# IPM_12V.net
KiCad netlist of a schematic drawn in EasyEDA Pro
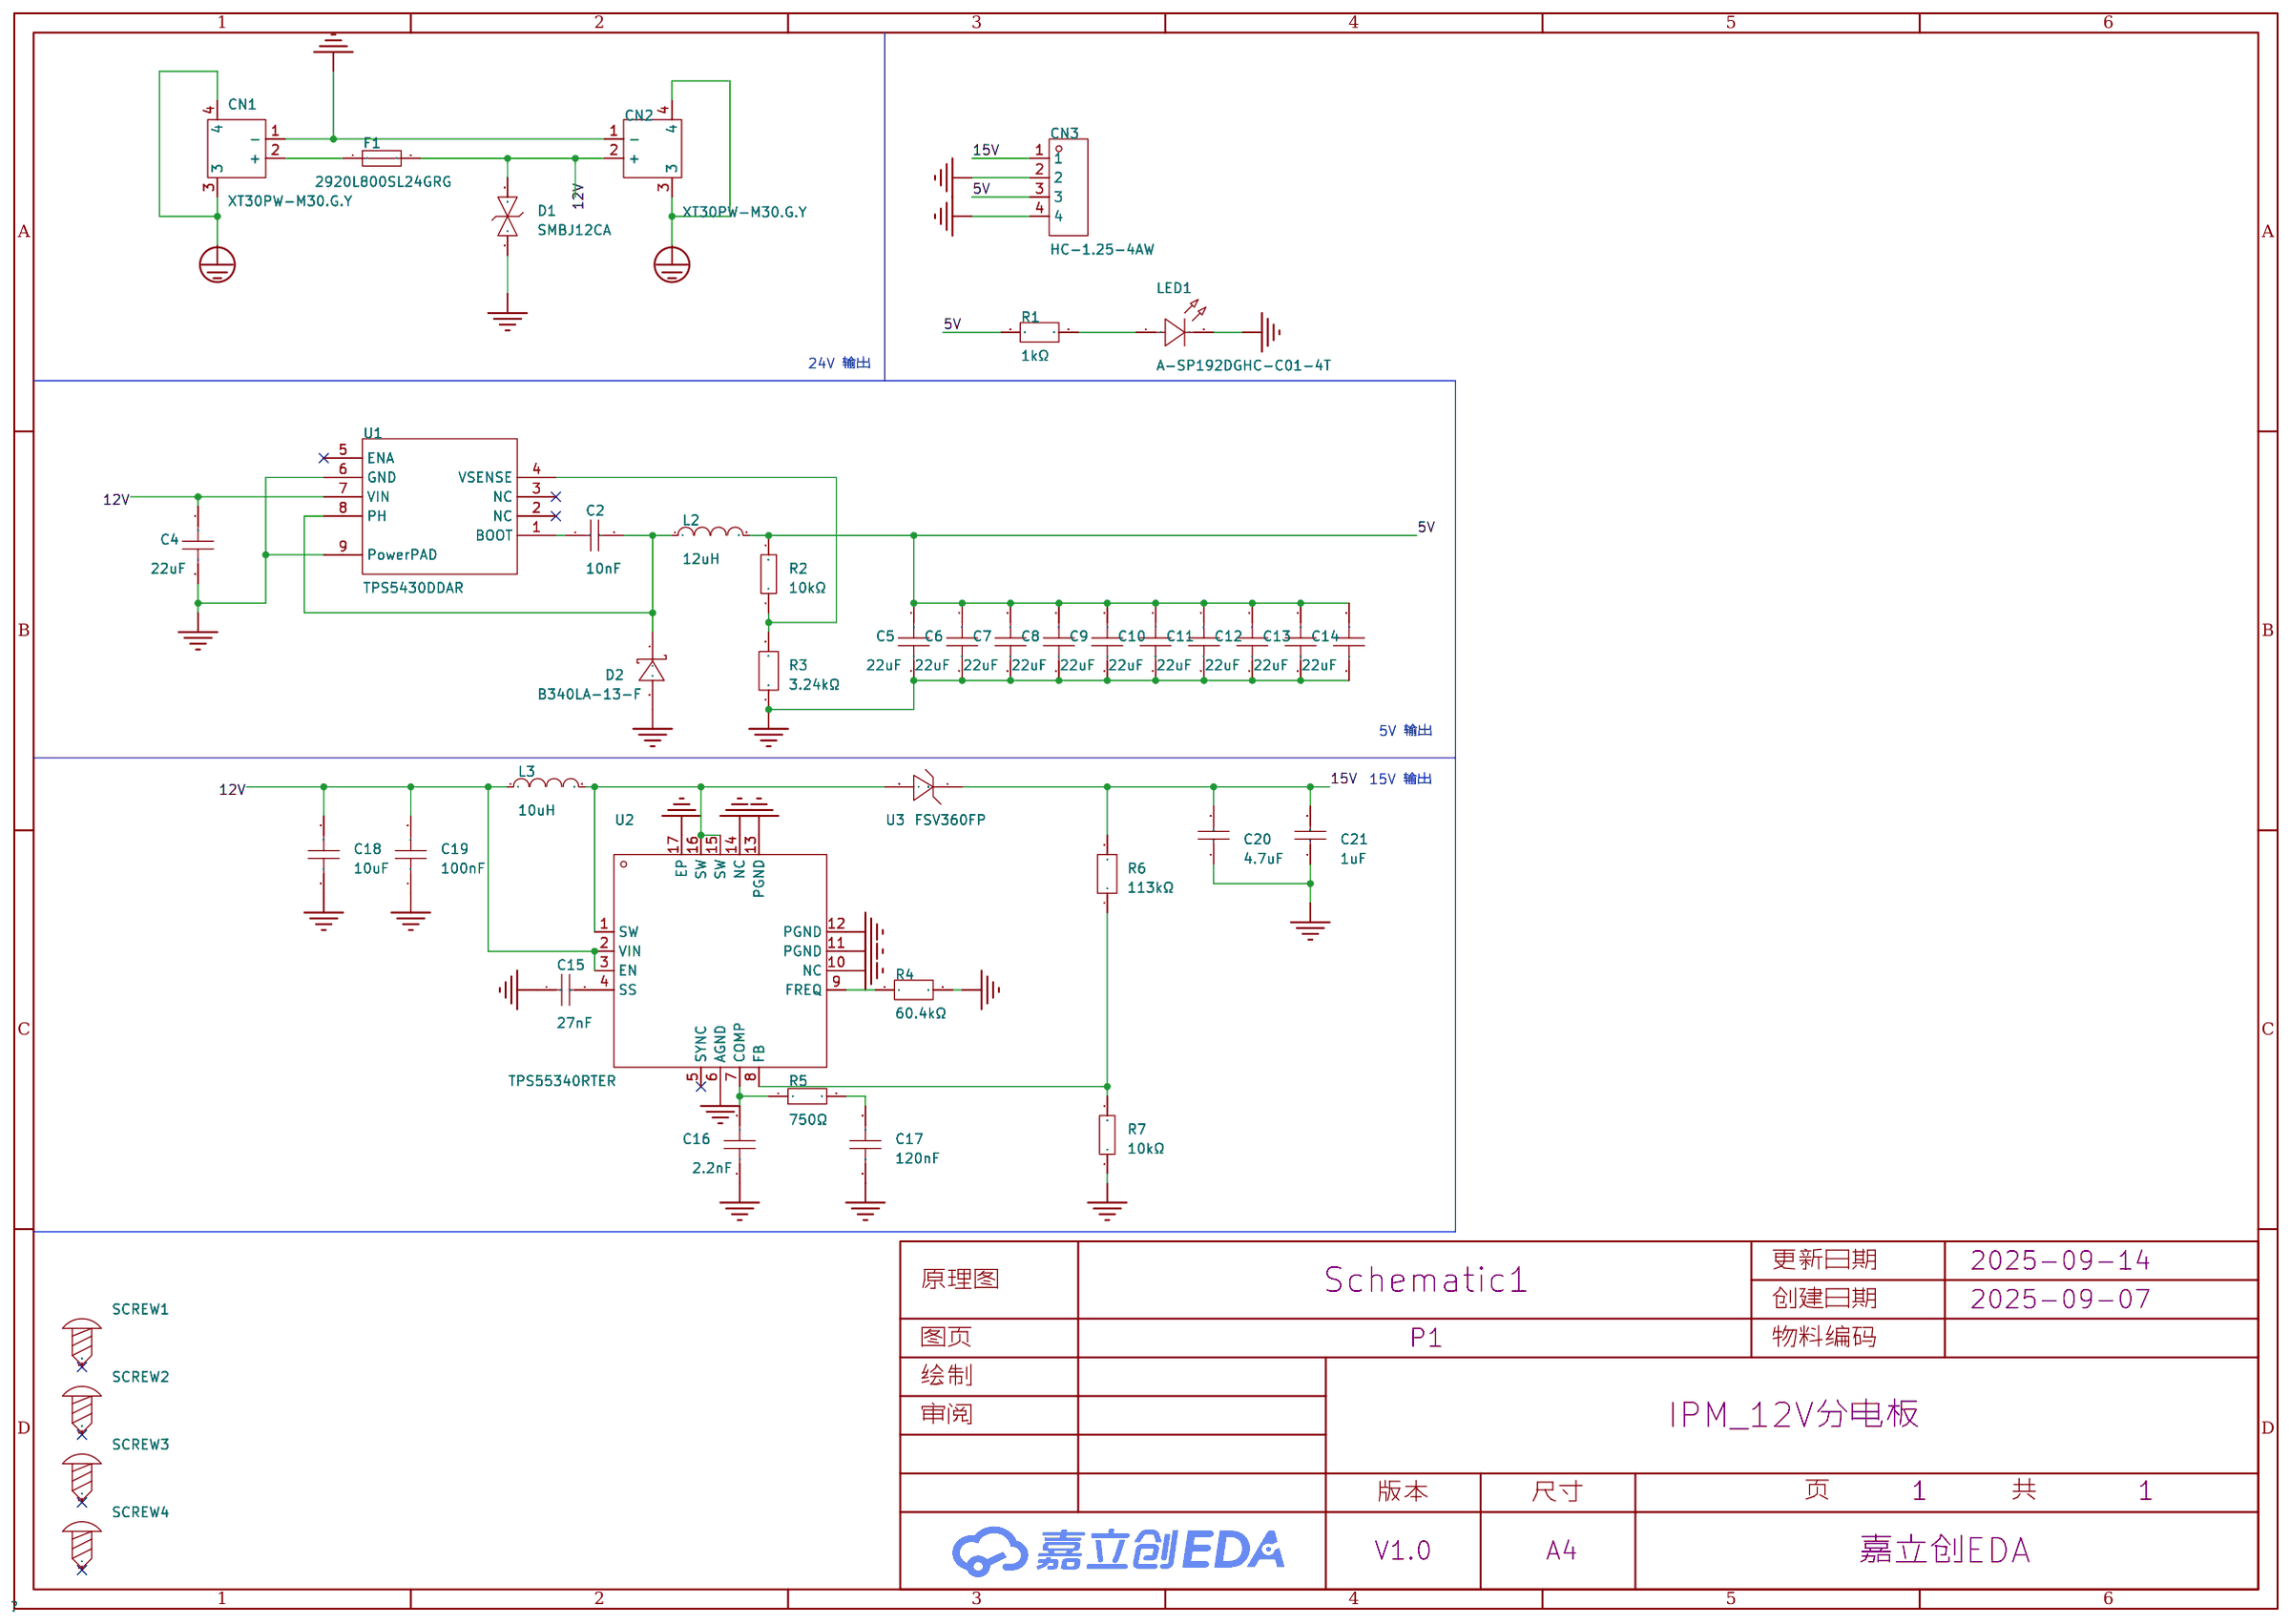
[diagram p0: schematic sheet]

(export (version "E")
  (design (tool "Eeschema 10.0.6"))
  (components
    (comp (ref "C2")
      (value "10nF")
      (footprint "easyedapro:C0603")
      (description "容值:10nF;精度:±10%;额定电压:50V;温度系数:X7R;")
      (fields
        (field (name "Manufacturer Part") "CL10B103KB8NNNC")
        (field (name "Manufacturer") "SAMSUNG(三星)")
      )
      (libsource (lib "easyedapro") (part "CL10B103KB8NNNC"))
    )
    (comp (ref "C4")
      (value "22uF")
      (footprint "easyedapro:C0603")
      (description "容值:22uF;精度:±20%;额定电压:16V;温度系数:X5R;")
      (fields
        (field (name "Manufacturer Part") "CL10A226MO7JZNC")
        (field (name "Manufacturer") "SAMSUNG(三星)")
      )
      (libsource (lib "easyedapro") (part "CL10A226MO7JZNC"))
    )
    (comp (ref "C5")
      (value "22uF")
      (footprint "easyedapro:C0603")
      (description "容值:22uF;精度:±20%;额定电压:16V;温度系数:X5R;")
      (fields
        (field (name "Manufacturer Part") "CL10A226MO7JZNC")
        (field (name "Manufacturer") "SAMSUNG(三星)")
      )
      (libsource (lib "easyedapro") (part "CL10A226MO7JZNC"))
    )
    (comp (ref "C6")
      (value "22uF")
      (footprint "easyedapro:C0603")
      (description "容值:22uF;精度:±20%;额定电压:16V;温度系数:X5R;")
      (fields
        (field (name "Manufacturer Part") "CL10A226MO7JZNC")
        (field (name "Manufacturer") "SAMSUNG(三星)")
      )
      (libsource (lib "easyedapro") (part "CL10A226MO7JZNC"))
    )
    (comp (ref "C7")
      (value "22uF")
      (footprint "easyedapro:C0603")
      (description "容值:22uF;精度:±20%;额定电压:16V;温度系数:X5R;")
      (fields
        (field (name "Manufacturer Part") "CL10A226MO7JZNC")
        (field (name "Manufacturer") "SAMSUNG(三星)")
      )
      (libsource (lib "easyedapro") (part "CL10A226MO7JZNC"))
    )
    (comp (ref "C8")
      (value "22uF")
      (footprint "easyedapro:C0603")
      (description "容值:22uF;精度:±20%;额定电压:16V;温度系数:X5R;")
      (fields
        (field (name "Manufacturer Part") "CL10A226MO7JZNC")
        (field (name "Manufacturer") "SAMSUNG(三星)")
      )
      (libsource (lib "easyedapro") (part "CL10A226MO7JZNC"))
    )
    (comp (ref "C9")
      (value "22uF")
      (footprint "easyedapro:C0603")
      (description "容值:22uF;精度:±20%;额定电压:16V;温度系数:X5R;")
      (fields
        (field (name "Manufacturer Part") "CL10A226MO7JZNC")
        (field (name "Manufacturer") "SAMSUNG(三星)")
      )
      (libsource (lib "easyedapro") (part "CL10A226MO7JZNC"))
    )
    (comp (ref "C10")
      (value "22uF")
      (footprint "easyedapro:C0603")
      (description "容值:22uF;精度:±20%;额定电压:16V;温度系数:X5R;")
      (fields
        (field (name "Manufacturer Part") "CL10A226MO7JZNC")
        (field (name "Manufacturer") "SAMSUNG(三星)")
      )
      (libsource (lib "easyedapro") (part "CL10A226MO7JZNC"))
    )
    (comp (ref "C11")
      (value "22uF")
      (footprint "easyedapro:C0603")
      (description "容值:22uF;精度:±20%;额定电压:16V;温度系数:X5R;")
      (fields
        (field (name "Manufacturer Part") "CL10A226MO7JZNC")
        (field (name "Manufacturer") "SAMSUNG(三星)")
      )
      (libsource (lib "easyedapro") (part "CL10A226MO7JZNC"))
    )
    (comp (ref "C12")
      (value "22uF")
      (footprint "easyedapro:C0603")
      (description "容值:22uF;精度:±20%;额定电压:16V;温度系数:X5R;")
      (fields
        (field (name "Manufacturer Part") "CL10A226MO7JZNC")
        (field (name "Manufacturer") "SAMSUNG(三星)")
      )
      (libsource (lib "easyedapro") (part "CL10A226MO7JZNC"))
    )
    (comp (ref "C13")
      (value "22uF")
      (footprint "easyedapro:C0603")
      (description "容值:22uF;精度:±20%;额定电压:16V;温度系数:X5R;")
      (fields
        (field (name "Manufacturer Part") "CL10A226MO7JZNC")
        (field (name "Manufacturer") "SAMSUNG(三星)")
      )
      (libsource (lib "easyedapro") (part "CL10A226MO7JZNC"))
    )
    (comp (ref "C14")
      (value "22uF")
      (footprint "easyedapro:C0603")
      (description "容值:22uF;精度:±20%;额定电压:16V;温度系数:X5R;")
      (fields
        (field (name "Manufacturer Part") "CL10A226MO7JZNC")
        (field (name "Manufacturer") "SAMSUNG(三星)")
      )
      (libsource (lib "easyedapro") (part "CL10A226MO7JZNC"))
    )
    (comp (ref "C15")
      (value "27nF")
      (footprint "easyedapro:C0603")
      (description "容值:27nF;精度:±10%;额定电压:50V;温度系数:X7R;")
      (fields
        (field (name "Manufacturer Part") "CC0603KRX7R9BB273")
        (field (name "Manufacturer") "YAGEO(国巨)")
      )
      (libsource (lib "easyedapro") (part "CC0603KRX7R9BB273"))
    )
    (comp (ref "C16")
      (value "2.2nF")
      (footprint "easyedapro:C0603")
      (description "容值:2.2nF;精度:±5%;额定电压:50V;材质(温度系数):C0G;")
      (fields
        (field (name "Manufacturer Part") "GRM1885C1H222JA01D")
        (field (name "Manufacturer") "muRata(村田)")
      )
      (libsource (lib "easyedapro") (part "GRM1885C1H222JA01D"))
    )
    (comp (ref "C17")
      (value "120nF")
      (footprint "easyedapro:C0603")
      (description "容值:120nF;精度:±10%;额定电压:50V;温度系数:X7R;")
      (fields
        (field (name "Manufacturer Part") "CGA0603X7R124K500JT")
        (field (name "Manufacturer") "HRE(芯声)")
      )
      (libsource (lib "easyedapro") (part "CGA0603X7R124K500JT"))
    )
    (comp (ref "C18")
      (value "10uF")
      (footprint "easyedapro:C0603")
      (description "容值:10uF;精度:±20%;额定电压:25V;温度系数:X5R;")
      (fields
        (field (name "Manufacturer Part") "CL10A106MA8NRNC")
        (field (name "Manufacturer") "SAMSUNG(三星)")
      )
      (libsource (lib "easyedapro") (part "CL10A106MA8NRNC"))
    )
    (comp (ref "C19")
      (value "100nF")
      (footprint "easyedapro:C0603")
      (description "容值:100nF;精度:±10%;额定电压:50V;温度系数:X7R;")
      (fields
        (field (name "Manufacturer Part") "CL10B104KB8NNNC")
        (field (name "Manufacturer") "SAMSUNG(三星)")
      )
      (libsource (lib "easyedapro") (part "CL10B104KB8NNNC"))
    )
    (comp (ref "C20")
      (value "4.7uF")
      (footprint "easyedapro:C0805")
      (description "容值:4.7uF;精度:±10%;额定电压:50V;温度系数:X5R;")
      (fields
        (field (name "Manufacturer Part") "CL21A475KBQNNNE")
        (field (name "Manufacturer") "SAMSUNG(三星)")
      )
      (libsource (lib "easyedapro") (part "CL21A475KBQNNNE"))
    )
    (comp (ref "C21")
      (value "1uF")
      (footprint "easyedapro:C0805")
      (description "容值:1uF;精度:±10%;额定电压:50V;温度系数:X7R;")
      (fields
        (field (name "Manufacturer Part") "CL21B105KBFNNNE")
        (field (name "Manufacturer") "SAMSUNG(三星)")
      )
      (libsource (lib "easyedapro") (part "CL21B105KBFNNNE"))
    )
    (comp (ref "CN1")
      (value "XT30PW-M30.G.Y")
      (footprint "easyedapro:CONN-TH_XT30PW-M")
      (description "类别:-;类型1:-;")
      (fields (field (name "Manufacturer") "AMASS(艾迈斯)"))
      (libsource (lib "easyedapro") (part "XT30PW-M"))
    )
    (comp (ref "CN2")
      (value "XT30PW-M30.G.Y")
      (footprint "easyedapro:CONN-TH_XT30PW-M")
      (description "类别:-;类型1:-;")
      (fields (field (name "Manufacturer") "AMASS(艾迈斯)"))
      (libsource (lib "easyedapro") (part "XT30PW-M"))
    )
    (comp (ref "CN3")
      (value "HC-1.25-4AW")
      (footprint "easyedapro:CONN-TH_4P-P1.25_HCTL_HC-1.25-4AW")
      (fields (field (name "Manufacturer") "HCTL(华灿天禄)"))
      (libsource (lib "easyedapro") (part "HC-1.25-4AW"))
    )
    (comp (ref "D1")
      (value "SMBJ12CA")
      (footprint "easyedapro:SMB_L4.6-W3.6-LS5.4-BI")
      (fields (field (name "Manufacturer") "R+O(宏嘉诚)"))
      (libsource (lib "easyedapro") (part "SMBJ12CA_C19077566"))
    )
    (comp (ref "D2")
      (value "B340LA-13-F")
      (footprint "easyedapro:SMA_L4.3-W2.6-LS5.2-RD")
      (description "正向压降(Vf):450mV@3A;直流反向耐压(Vr):40V;平均整流电流(Io):3A;")
      (fields (field (name "Manufacturer") "DIODES(美台)"))
      (libsource (lib "easyedapro") (part "B340LA-13-F"))
    )
    (comp (ref "F1")
      (value "2920L800SL24GRG")
      (footprint "easyedapro:F2920")
      (description "耐压(Vmax):24V;最大电流(Imax):50A;保持电流(Ihold):8A;跳闸电流(Itrip):16A;")
      (fields (field (name "Manufacturer") "LUTE(陆特)"))
      (libsource (lib "easyedapro") (part "2920L800SL24GRG"))
    )
    (comp (ref "L2")
      (value "12uH")
      (footprint "easyedapro:IND-SMD_L8.0-W8.0_FNR80XXS")
      (description "电感值:12uH;精度:±20%;额定电流:3A;饱和电流(Isat):4A;类型:磁胶屏蔽绕线合金电感;")
      (fields (field (name "Manufacturer Part") "FNR8040S120MT") (field (name "Manufacturer") "cjiang(长江微电)"))
      (libsource (lib "easyedapro") (part "FNR8040S120MT"))
    )
    (comp (ref "L3")
      (value "10uH")
      (footprint "easyedapro:IND-SMD_L5.4-W5.2_FXL0530")
      (description "电感值:10uH;精度:±20%;额定电流:3.2A;饱和电流(Isat):3.5A;类型:一体成型电感;")
      (fields (field (name "Manufacturer Part") "FXL0530-100-M") (field (name "Manufacturer") "cjiang(长江微电)"))
      (libsource (lib "easyedapro") (part "FXL0530-100-M"))
    )
    (comp (ref "LED1")
      (value "A-SP192DGHC-C01-4T")
      (footprint "easyedapro:LED0603-FD")
      (fields (field (name "Manufacturer") "Amicc(欧密格光电)"))
      (libsource (lib "easyedapro") (part "A-SP192DGHC-C01-4T"))
    )
    (comp (ref "R1")
      (value "1kΩ")
      (footprint "easyedapro:R0603")
      (description "电阻类型:厚膜电阻;阻值:1kΩ;精度:±1%;功率:100mW;工作电压:75V;温度系数:±100ppm/°C;")
      (fields (field (name "Manufacturer Part") "FRC0603F1001TS") (field (name "Manufacturer") "FOJAN(富捷)"))
      (libsource (lib "easyedapro") (part "FRC0603F1001TS"))
    )
    (comp (ref "R2")
      (value "10kΩ")
      (footprint "easyedapro:R0603")
      (description "电阻类型:厚膜电阻;阻值:10kΩ;精度:±1%;功率:100mW;工作电压:75V;温度系数:±100ppm/°C;")
      (fields
        (field (name "Manufacturer Part") "0603WAF1002T5E")
        (field (name "Manufacturer") "UNI-ROYAL(厚声)")
      )
      (libsource (lib "easyedapro") (part "0603WAF1002T5E"))
    )
    (comp (ref "R3")
      (value "3.24kΩ")
      (footprint "easyedapro:R0603")
      (description "电阻类型:厚膜电阻;阻值:3.24kΩ;精度:±1%;功率:100mW;工作电压:75V;温度系数:±100ppm/°C;")
      (fields (field (name "Manufacturer Part") "FRC0603F3241TS") (field (name "Manufacturer") "FOJAN(富捷)"))
      (libsource (lib "easyedapro") (part "FRC0603F3241TS"))
    )
    (comp (ref "R4")
      (value "60.4kΩ")
      (footprint "easyedapro:R0603")
      (description "电阻类型:薄膜电阻;阻值:60.4kΩ;精度:±0.1%;功率:100mW;温度系数:±25ppm/°C;")
      (fields (field (name "Manufacturer Part") "RT0603BRD0760K4L") (field (name "Manufacturer") "YAGEO(国巨)"))
      (libsource (lib "easyedapro") (part "RT0603BRD0760K4L"))
    )
    (comp (ref "R5")
      (value "750Ω")
      (footprint "easyedapro:R0603")
      (description "电阻类型:薄膜电阻;阻值:750Ω;精度:±0.1%;功率:100mW;工作电压:100V;温度系数:±25ppm/°C;")
      (fields (field (name "Manufacturer Part") "PTFR0603B750RP9") (field (name "Manufacturer") "RESI(开步睿思)"))
      (libsource (lib "easyedapro") (part "PTFR0603B750RP9"))
    )
    (comp (ref "R6")
      (value "113kΩ")
      (footprint "easyedapro:R0603")
      (description "电阻类型:薄膜电阻;阻值:113kΩ;精度:±0.1%;功率:100mW;工作电压:75V;温度系数:±25ppm/°C;")
      (fields (field (name "Manufacturer Part") "RT0603BRD07113KL") (field (name "Manufacturer") "YAGEO(国巨)"))
      (libsource (lib "easyedapro") (part "RT0603BRD07113KL"))
    )
    (comp (ref "R7")
      (value "10kΩ")
      (footprint "easyedapro:R0603")
      (description "电阻类型:厚膜电阻;阻值:10kΩ;精度:±1%;功率:100mW;工作电压:75V;温度系数:±100ppm/°C;")
      (fields
        (field (name "Manufacturer Part") "0603WAF1002T5E")
        (field (name "Manufacturer") "UNI-ROYAL(厚声)")
      )
      (libsource (lib "easyedapro") (part "0603WAF1002T5E"))
    )
    (comp (ref "SCREW1")
      (value "~")
      (footprint "easyedapro:M2螺丝")
      (libsource (lib "easyedapro") (part "螺丝孔"))
    )
    (comp (ref "SCREW2")
      (value "~")
      (footprint "easyedapro:M2螺丝")
      (libsource (lib "easyedapro") (part "螺丝孔"))
    )
    (comp (ref "SCREW3")
      (value "~")
      (footprint "easyedapro:M2螺丝")
      (libsource (lib "easyedapro") (part "螺丝孔"))
    )
    (comp (ref "SCREW4")
      (value "~")
      (footprint "easyedapro:M2螺丝")
      (libsource (lib "easyedapro") (part "螺丝孔"))
    )
    (comp (ref "U1")
      (value "TPS5430DDAR")
      (footprint "easyedapro:ESOP-8_L4.9-W3.9-P1.27-LS6.0-TL-EP")
      (description "功能类型:降压型;输出类型:可调;工作电压:5.5V~36V;输出电压:1.221V~32.04V;输出电流:3A;")
      (fields (field (name "Manufacturer") "TI(德州仪器)"))
      (libsource (lib "easyedapro") (part "TPS5430DDAR"))
    )
    (comp (ref "U2")
      (value "TPS55340RTER")
      (footprint "easyedapro:VQFN-16_L3.0-W3.0-P0.50-BL-EP1.7")
      (description "功能类型:升压型;输出类型:可调;工作电压:2.9V~32V;输出电压:2.9V~38V;输出电流:5.25A;")
      (fields (field (name "Manufacturer") "TI(德州仪器)"))
      (libsource (lib "easyedapro") (part "TPS55340RTER"))
    )
    (comp (ref "U3")
      (value "FSV360FP")
      (footprint "easyedapro:POWERDI-123_L2.8-W1.8-LS3.7-RD-1")
      (description "二极管配置:独立式;正向压降(Vf):650mV@3A;直流反向耐压(Vr):60V;整流电流:3A;")
      (fields (field (name "Manufacturer") "onsemi(安森美)"))
      (libsource (lib "easyedapro") (part "FSV360FP"))
    )
  )
  (nets
    (net (code "1") (name "/5V") (class "Default")
      (node (ref "C10") (pin "1") (pinfunction "1_1") (pintype "unspecified"))
      (node (ref "C11") (pin "1") (pinfunction "1_1") (pintype "unspecified"))
      (node (ref "C12") (pin "1") (pinfunction "1_1") (pintype "unspecified"))
      (node (ref "C13") (pin "1") (pinfunction "1_1") (pintype "unspecified"))
      (node (ref "C14") (pin "1") (pinfunction "1_1") (pintype "unspecified"))
      (node (ref "C5") (pin "1") (pinfunction "1_1") (pintype "unspecified"))
      (node (ref "C6") (pin "1") (pinfunction "1_1") (pintype "unspecified"))
      (node (ref "C7") (pin "1") (pinfunction "1_1") (pintype "unspecified"))
      (node (ref "C8") (pin "1") (pinfunction "1_1") (pintype "unspecified"))
      (node (ref "C9") (pin "1") (pinfunction "1_1") (pintype "unspecified"))
      (node (ref "CN3") (pin "3") (pinfunction "3_3") (pintype "unspecified"))
      (node (ref "L2") (pin "2") (pinfunction "2_2") (pintype "unspecified"))
      (node (ref "R1") (pin "1") (pinfunction "1_1") (pintype "unspecified"))
      (node (ref "R2") (pin "2") (pinfunction "2_2") (pintype "input"))
    )
    (net (code "2") (name "/12V") (class "Default")
      (node (ref "C18") (pin "2") (pinfunction "2_2") (pintype "unspecified"))
      (node (ref "C19") (pin "2") (pinfunction "2_2") (pintype "unspecified"))
      (node (ref "C4") (pin "1") (pinfunction "1_1") (pintype "unspecified"))
      (node (ref "CN2") (pin "2") (pinfunction "+_2") (pintype "unspecified"))
      (node (ref "D1") (pin "2") (pinfunction "2_2") (pintype "unspecified"))
      (node (ref "F1") (pin "2") (pinfunction "2_2") (pintype "unspecified"))
      (node (ref "L3") (pin "1") (pinfunction "1_1") (pintype "unspecified"))
      (node (ref "U1") (pin "7") (pinfunction "VIN_7") (pintype "unspecified"))
      (node (ref "U2") (pin "2") (pinfunction "VIN_2") (pintype "unspecified"))
      (node (ref "U2") (pin "3") (pinfunction "EN_3") (pintype "unspecified"))
    )
    (net (code "3") (name "/15V") (class "Default")
      (node (ref "C20") (pin "2") (pinfunction "2_2") (pintype "input"))
      (node (ref "C21") (pin "2") (pinfunction "2_2") (pintype "input"))
      (node (ref "CN3") (pin "1") (pinfunction "1_1") (pintype "unspecified"))
      (node (ref "R6") (pin "2") (pinfunction "2_2") (pintype "unspecified"))
      (node (ref "U3") (pin "1") (pinfunction "C_1") (pintype "unspecified"))
    )
    (net (code "4") (name "GND") (class "Default")
      (node (ref "C10") (pin "2") (pinfunction "2_2") (pintype "unspecified"))
      (node (ref "C11") (pin "2") (pinfunction "2_2") (pintype "unspecified"))
      (node (ref "C12") (pin "2") (pinfunction "2_2") (pintype "unspecified"))
      (node (ref "C13") (pin "2") (pinfunction "2_2") (pintype "unspecified"))
      (node (ref "C14") (pin "2") (pinfunction "2_2") (pintype "unspecified"))
      (node (ref "C15") (pin "1") (pinfunction "1_1") (pintype "input"))
      (node (ref "C16") (pin "1") (pinfunction "1_1") (pintype "unspecified"))
      (node (ref "C17") (pin "1") (pinfunction "1_1") (pintype "unspecified"))
      (node (ref "C18") (pin "1") (pinfunction "1_1") (pintype "unspecified"))
      (node (ref "C19") (pin "1") (pinfunction "1_1") (pintype "unspecified"))
      (node (ref "C20") (pin "1") (pinfunction "1_1") (pintype "input"))
      (node (ref "C21") (pin "1") (pinfunction "1_1") (pintype "input"))
      (node (ref "C4") (pin "2") (pinfunction "2_2") (pintype "unspecified"))
      (node (ref "C5") (pin "2") (pinfunction "2_2") (pintype "unspecified"))
      (node (ref "C6") (pin "2") (pinfunction "2_2") (pintype "unspecified"))
      (node (ref "C7") (pin "2") (pinfunction "2_2") (pintype "unspecified"))
      (node (ref "C8") (pin "2") (pinfunction "2_2") (pintype "unspecified"))
      (node (ref "C9") (pin "2") (pinfunction "2_2") (pintype "unspecified"))
      (node (ref "CN1") (pin "1") (pinfunction "-_1") (pintype "unspecified"))
      (node (ref "CN2") (pin "1") (pinfunction "-_1") (pintype "unspecified"))
      (node (ref "CN3") (pin "2") (pinfunction "2_2") (pintype "unspecified"))
      (node (ref "CN3") (pin "4") (pinfunction "4_4") (pintype "unspecified"))
      (node (ref "D1") (pin "1") (pinfunction "1_1") (pintype "unspecified"))
      (node (ref "D2") (pin "2") (pinfunction "A_2") (pintype "unspecified"))
      (node (ref "LED1") (pin "2") (pinfunction "K_2") (pintype "unspecified"))
      (node (ref "R3") (pin "1") (pinfunction "1_1") (pintype "unspecified"))
      (node (ref "R4") (pin "2") (pinfunction "2_2") (pintype "unspecified"))
      (node (ref "R7") (pin "1") (pinfunction "1_1") (pintype "input"))
      (node (ref "U1") (pin "6") (pinfunction "GND_6") (pintype "unspecified"))
      (node (ref "U1") (pin "9") (pinfunction "PowerPAD_9") (pintype "unspecified"))
      (node (ref "U2") (pin "10") (pinfunction "NC_10") (pintype "unspecified"))
      (node (ref "U2") (pin "11") (pinfunction "PGND_11") (pintype "unspecified"))
      (node (ref "U2") (pin "12") (pinfunction "PGND_12") (pintype "unspecified"))
      (node (ref "U2") (pin "13") (pinfunction "PGND_13") (pintype "unspecified"))
      (node (ref "U2") (pin "14") (pinfunction "NC_14") (pintype "unspecified"))
      (node (ref "U2") (pin "17") (pinfunction "EP_17") (pintype "unspecified"))
      (node (ref "U2") (pin "6") (pinfunction "AGND_6") (pintype "unspecified"))
    )
    (net (code "5") (name "Net-(C17-Pad2)") (class "Default")
      (node (ref "C17") (pin "2") (pinfunction "2_2") (pintype "unspecified"))
      (node (ref "R5") (pin "2") (pinfunction "2_2") (pintype "unspecified"))
    )
    (net (code "6") (name "Net-(CN1-+)") (class "Default")
      (node (ref "CN1") (pin "2") (pinfunction "+_2") (pintype "unspecified"))
      (node (ref "F1") (pin "1") (pinfunction "1_1") (pintype "unspecified"))
    )
    (net (code "7") (name "Net-(D2-K)") (class "Default")
      (node (ref "C2") (pin "2") (pinfunction "2_2") (pintype "input"))
      (node (ref "D2") (pin "1") (pinfunction "K_1") (pintype "unspecified"))
      (node (ref "L2") (pin "1") (pinfunction "1_1") (pintype "unspecified"))
      (node (ref "U1") (pin "8") (pinfunction "PH_8") (pintype "unspecified"))
    )
    (net (code "8") (name "Net-(LED1-A)") (class "Default")
      (node (ref "LED1") (pin "1") (pinfunction "A_1") (pintype "unspecified"))
      (node (ref "R1") (pin "2") (pinfunction "2_2") (pintype "unspecified"))
    )
    (net (code "9") (name "Net-(U1-BOOT)") (class "Default")
      (node (ref "C2") (pin "1") (pinfunction "1_1") (pintype "input"))
      (node (ref "U1") (pin "1") (pinfunction "BOOT_1") (pintype "unspecified"))
    )
    (net (code "10") (name "Net-(U1-VSENSE)") (class "Default")
      (node (ref "R2") (pin "1") (pinfunction "1_1") (pintype "input"))
      (node (ref "R3") (pin "2") (pinfunction "2_2") (pintype "unspecified"))
      (node (ref "U1") (pin "4") (pinfunction "VSENSE_4") (pintype "unspecified"))
    )
    (net (code "11") (name "Net-(U2-COMP)") (class "Default")
      (node (ref "C16") (pin "2") (pinfunction "2_2") (pintype "unspecified"))
      (node (ref "R5") (pin "1") (pinfunction "1_1") (pintype "unspecified"))
      (node (ref "U2") (pin "7") (pinfunction "COMP_7") (pintype "unspecified"))
    )
    (net (code "12") (name "Net-(U2-FB)") (class "Default")
      (node (ref "R6") (pin "1") (pinfunction "1_1") (pintype "unspecified"))
      (node (ref "R7") (pin "2") (pinfunction "2_2") (pintype "input"))
      (node (ref "U2") (pin "8") (pinfunction "FB_8") (pintype "unspecified"))
    )
    (net (code "13") (name "Net-(U2-FREQ)") (class "Default")
      (node (ref "R4") (pin "1") (pinfunction "1_1") (pintype "unspecified"))
      (node (ref "U2") (pin "9") (pinfunction "FREQ_9") (pintype "unspecified"))
    )
    (net (code "14") (name "Net-(U2-SS)") (class "Default")
      (node (ref "C15") (pin "2") (pinfunction "2_2") (pintype "input"))
      (node (ref "U2") (pin "4") (pinfunction "SS_4") (pintype "unspecified"))
    )
    (net (code "15") (name "Net-(U3-A)") (class "Default")
      (node (ref "L3") (pin "2") (pinfunction "2_2") (pintype "unspecified"))
      (node (ref "U2") (pin "1") (pinfunction "SW_1") (pintype "unspecified"))
      (node (ref "U2") (pin "15") (pinfunction "SW_15") (pintype "unspecified"))
      (node (ref "U2") (pin "16") (pinfunction "SW_16") (pintype "unspecified"))
      (node (ref "U3") (pin "2") (pinfunction "A_2") (pintype "unspecified"))
    )
    (net (code "16") (name "PGND") (class "Default")
      (node (ref "CN1") (pin "3") (pinfunction "3_3") (pintype "unspecified"))
      (node (ref "CN1") (pin "4") (pinfunction "4_4") (pintype "unspecified"))
      (node (ref "CN2") (pin "3") (pinfunction "3_3") (pintype "unspecified"))
      (node (ref "CN2") (pin "4") (pinfunction "4_4") (pintype "unspecified"))
    )
    (net (code "17") (name "unconnected-(SCREW1-Pad1)") (class "Default")
      (node (ref "SCREW1") (pin "1") (pinfunction "1_1") (pintype "input+no_connect"))
    )
    (net (code "18") (name "unconnected-(SCREW2-Pad1)") (class "Default")
      (node (ref "SCREW2") (pin "1") (pinfunction "1_1") (pintype "input+no_connect"))
    )
    (net (code "19") (name "unconnected-(SCREW3-Pad1)") (class "Default")
      (node (ref "SCREW3") (pin "1") (pinfunction "1_1") (pintype "input+no_connect"))
    )
    (net (code "20") (name "unconnected-(SCREW4-Pad1)") (class "Default")
      (node (ref "SCREW4") (pin "1") (pinfunction "1_1") (pintype "input+no_connect"))
    )
    (net (code "21") (name "unconnected-(U1-ENA-Pad5)") (class "Default")
      (node (ref "U1") (pin "5") (pinfunction "ENA_5") (pintype "unspecified+no_connect"))
    )
    (net (code "22") (name "unconnected-(U1-NC-Pad2)") (class "Default")
      (node (ref "U1") (pin "2") (pinfunction "NC_2") (pintype "unspecified+no_connect"))
    )
    (net (code "23") (name "unconnected-(U1-NC-Pad3)") (class "Default")
      (node (ref "U1") (pin "3") (pinfunction "NC_3") (pintype "unspecified+no_connect"))
    )
    (net (code "24") (name "unconnected-(U2-SYNC-Pad5)") (class "Default")
      (node (ref "U2") (pin "5") (pinfunction "SYNC_5") (pintype "unspecified+no_connect"))
    )
  )
)
